# BigBus.net
KiCad netlist of a schematic drawn in EAGLE
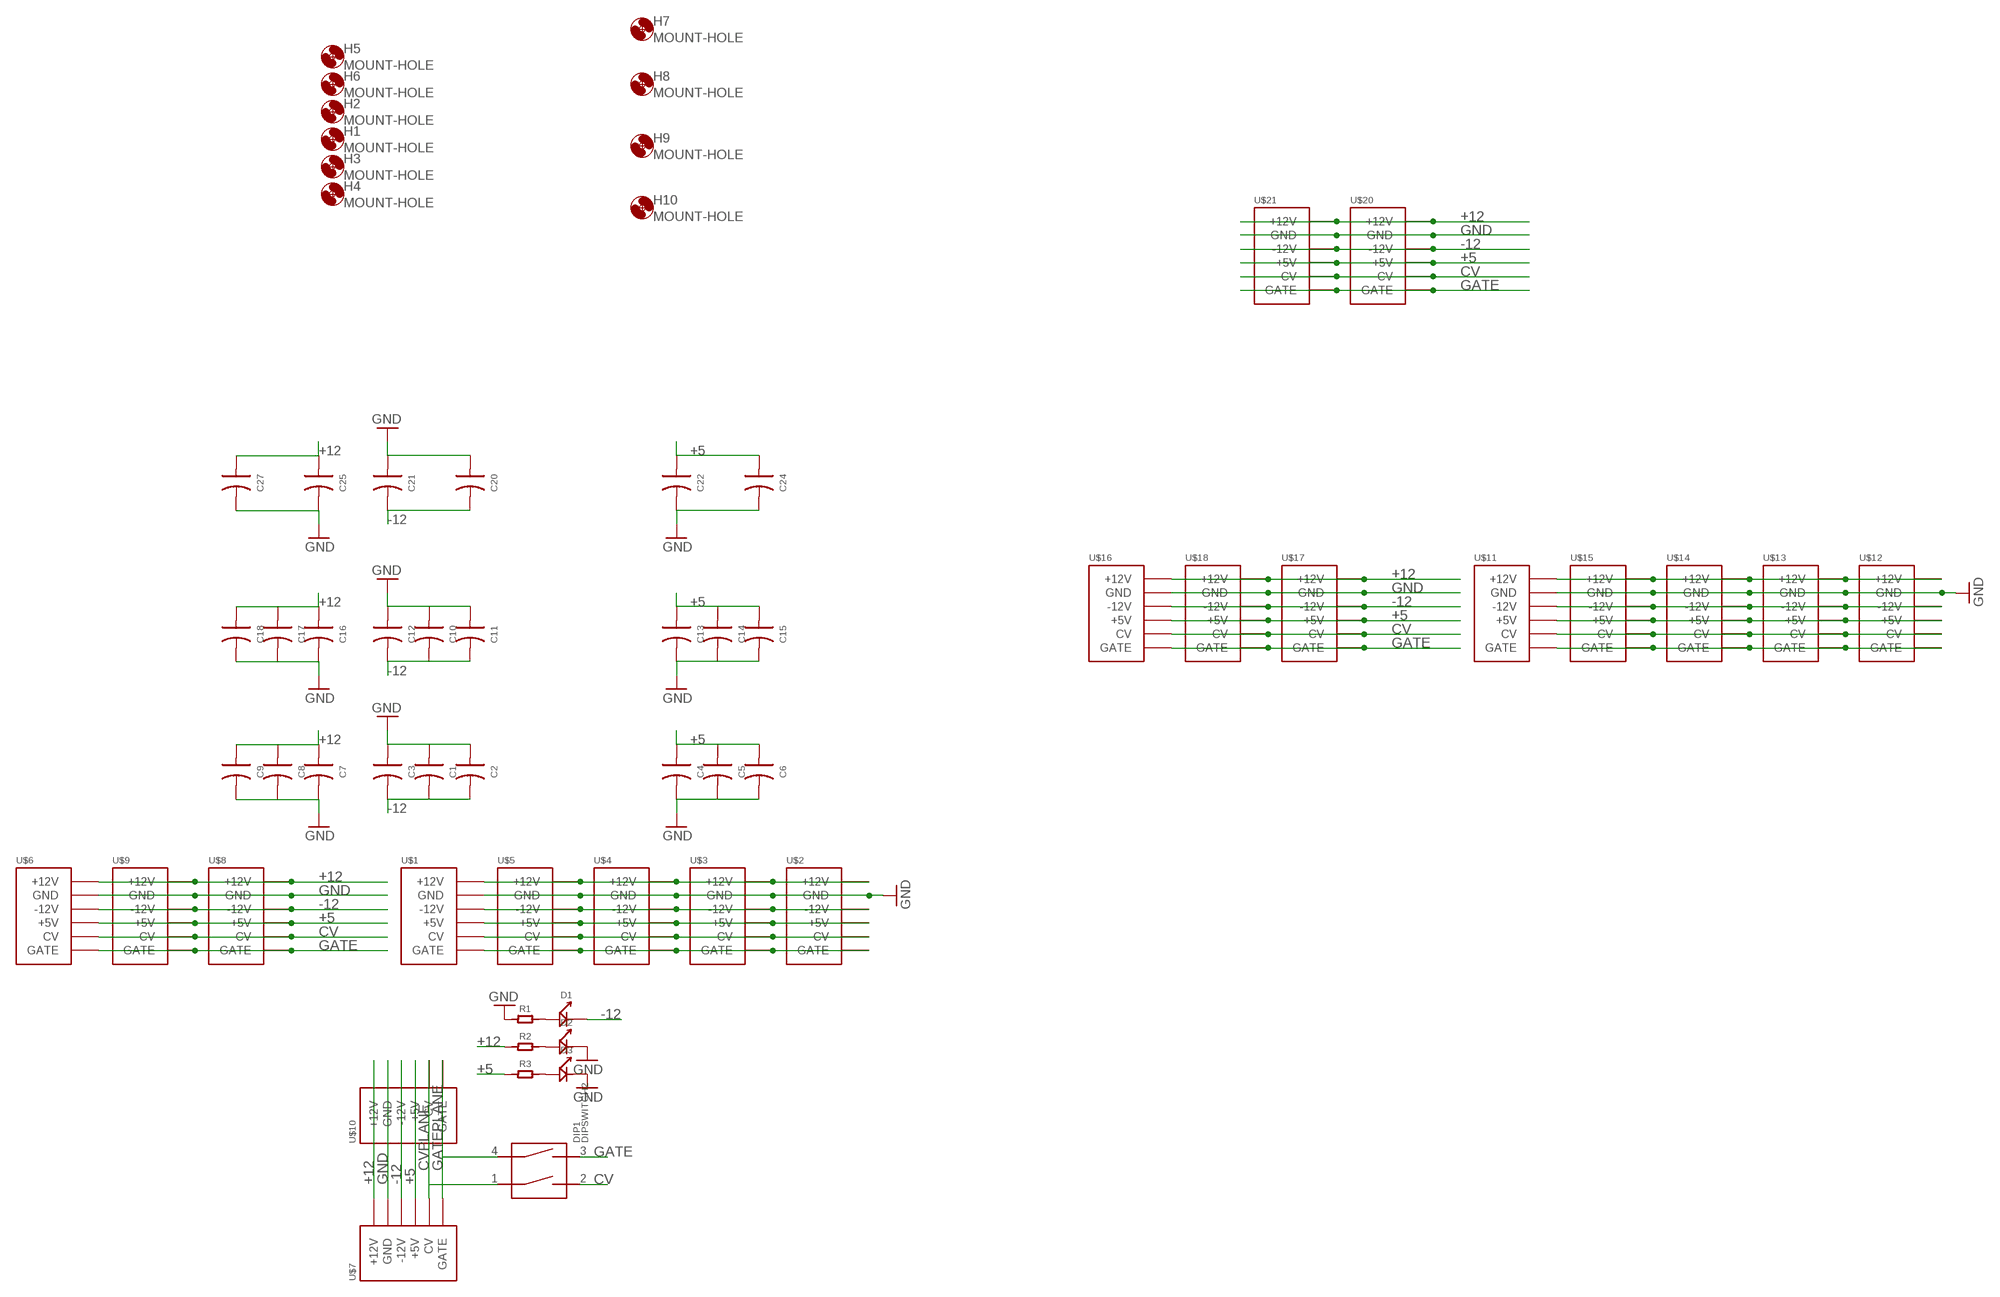
[diagram p0: schematic, sheet 1]

(export (version "E")
  (design (tool "Eeschema 10.0.6"))
  (components
    (comp (ref "C1")
      (value "C-POLAR-A")
      (footprint "eagle-import:AVX-A")
      (libsource (lib "eagle-import") (part "C-POLAR-A"))
    )
    (comp (ref "C2")
      (value "C-POLAR-A")
      (footprint "eagle-import:AVX-A")
      (libsource (lib "eagle-import") (part "C-POLAR-A"))
    )
    (comp (ref "C3")
      (value "C-POLAR-A")
      (footprint "eagle-import:AVX-A")
      (libsource (lib "eagle-import") (part "C-POLAR-A"))
    )
    (comp (ref "C4")
      (value "C-POLAR-A")
      (footprint "eagle-import:AVX-A")
      (libsource (lib "eagle-import") (part "C-POLAR-A"))
    )
    (comp (ref "C5")
      (value "C-POLAR-A")
      (footprint "eagle-import:AVX-A")
      (libsource (lib "eagle-import") (part "C-POLAR-A"))
    )
    (comp (ref "C6")
      (value "C-POLAR-A")
      (footprint "eagle-import:AVX-A")
      (libsource (lib "eagle-import") (part "C-POLAR-A"))
    )
    (comp (ref "C7")
      (value "C-POLAR-A")
      (footprint "eagle-import:AVX-A")
      (libsource (lib "eagle-import") (part "C-POLAR-A"))
    )
    (comp (ref "C8")
      (value "C-POLAR-A")
      (footprint "eagle-import:AVX-A")
      (libsource (lib "eagle-import") (part "C-POLAR-A"))
    )
    (comp (ref "C9")
      (value "C-POLAR-A")
      (footprint "eagle-import:AVX-A")
      (libsource (lib "eagle-import") (part "C-POLAR-A"))
    )
    (comp (ref "C10")
      (value "C-POLAR-A")
      (footprint "eagle-import:AVX-A")
      (libsource (lib "eagle-import") (part "C-POLAR-A"))
    )
    (comp (ref "C11")
      (value "C-POLAR-A")
      (footprint "eagle-import:AVX-A")
      (libsource (lib "eagle-import") (part "C-POLAR-A"))
    )
    (comp (ref "C12")
      (value "C-POLAR-A")
      (footprint "eagle-import:AVX-A")
      (libsource (lib "eagle-import") (part "C-POLAR-A"))
    )
    (comp (ref "C13")
      (value "C-POLAR-A")
      (footprint "eagle-import:AVX-A")
      (libsource (lib "eagle-import") (part "C-POLAR-A"))
    )
    (comp (ref "C14")
      (value "C-POLAR-A")
      (footprint "eagle-import:AVX-A")
      (libsource (lib "eagle-import") (part "C-POLAR-A"))
    )
    (comp (ref "C15")
      (value "C-POLAR-A")
      (footprint "eagle-import:AVX-A")
      (libsource (lib "eagle-import") (part "C-POLAR-A"))
    )
    (comp (ref "C16")
      (value "C-POLAR-A")
      (footprint "eagle-import:AVX-A")
      (libsource (lib "eagle-import") (part "C-POLAR-A"))
    )
    (comp (ref "C17")
      (value "C-POLAR-A")
      (footprint "eagle-import:AVX-A")
      (libsource (lib "eagle-import") (part "C-POLAR-A"))
    )
    (comp (ref "C18")
      (value "C-POLAR-A")
      (footprint "eagle-import:AVX-A")
      (libsource (lib "eagle-import") (part "C-POLAR-A"))
    )
    (comp (ref "C20")
      (value "C-POLAR-A")
      (footprint "eagle-import:AVX-A")
      (libsource (lib "eagle-import") (part "C-POLAR-A"))
    )
    (comp (ref "C21")
      (value "C-POLAR-A")
      (footprint "eagle-import:AVX-A")
      (libsource (lib "eagle-import") (part "C-POLAR-A"))
    )
    (comp (ref "C22")
      (value "C-POLAR-A")
      (footprint "eagle-import:AVX-A")
      (libsource (lib "eagle-import") (part "C-POLAR-A"))
    )
    (comp (ref "C24")
      (value "C-POLAR-A")
      (footprint "eagle-import:AVX-A")
      (libsource (lib "eagle-import") (part "C-POLAR-A"))
    )
    (comp (ref "C25")
      (value "C-POLAR-A")
      (footprint "eagle-import:AVX-A")
      (libsource (lib "eagle-import") (part "C-POLAR-A"))
    )
    (comp (ref "C27")
      (value "C-POLAR-A")
      (footprint "eagle-import:AVX-A")
      (libsource (lib "eagle-import") (part "C-POLAR-A"))
    )
    (comp (ref "D1")
      (value "LED")
      (footprint "eagle-import:LED0603")
      (libsource (lib "eagle-import") (part "LED"))
    )
    (comp (ref "D2")
      (value "LED")
      (footprint "eagle-import:LED0603")
      (libsource (lib "eagle-import") (part "LED"))
    )
    (comp (ref "D3")
      (value "LED")
      (footprint "eagle-import:LED0603")
      (libsource (lib "eagle-import") (part "LED"))
    )
    (comp (ref "DIP1")
      (value "DIPSWITCH2")
      (footprint "eagle-import:DIPSWITCH2")
      (libsource (lib "eagle-import") (part "DIPSWITCH2"))
    )
    (comp (ref "H1")
      (value "MOUNT-HOLE")
      (footprint "eagle-import:3.2-NOMARKINGS-SMALLSAFEZONE")
      (libsource (lib "eagle-import") (part "MOUNT-HOLE"))
    )
    (comp (ref "H2")
      (value "MOUNT-HOLE")
      (footprint "eagle-import:3.2-NOMARKINGS-SMALLSAFEZONE")
      (libsource (lib "eagle-import") (part "MOUNT-HOLE"))
    )
    (comp (ref "H3")
      (value "MOUNT-HOLE")
      (footprint "eagle-import:3.2-NOMARKINGS-SMALLSAFEZONE")
      (libsource (lib "eagle-import") (part "MOUNT-HOLE"))
    )
    (comp (ref "H4")
      (value "MOUNT-HOLE")
      (footprint "eagle-import:3.2-NOMARKINGS-SMALLSAFEZONE")
      (libsource (lib "eagle-import") (part "MOUNT-HOLE"))
    )
    (comp (ref "H5")
      (value "MOUNT-HOLE")
      (footprint "eagle-import:3.2-NOMARKINGS-SMALLSAFEZONE")
      (libsource (lib "eagle-import") (part "MOUNT-HOLE"))
    )
    (comp (ref "H6")
      (value "MOUNT-HOLE")
      (footprint "eagle-import:3.2-NOMARKINGS-SMALLSAFEZONE")
      (libsource (lib "eagle-import") (part "MOUNT-HOLE"))
    )
    (comp (ref "H7")
      (value "MOUNT-HOLE")
      (footprint "eagle-import:3.2-NOMARKINGS-SMALLSAFEZONE")
      (libsource (lib "eagle-import") (part "MOUNT-HOLE"))
    )
    (comp (ref "H8")
      (value "MOUNT-HOLE")
      (footprint "eagle-import:3.2-NOMARKINGS-SMALLSAFEZONE")
      (libsource (lib "eagle-import") (part "MOUNT-HOLE"))
    )
    (comp (ref "H9")
      (value "MOUNT-HOLE")
      (footprint "eagle-import:3.2-NOMARKINGS-SMALLSAFEZONE")
      (libsource (lib "eagle-import") (part "MOUNT-HOLE"))
    )
    (comp (ref "H10")
      (value "MOUNT-HOLE")
      (footprint "eagle-import:3.2-NOMARKINGS-SMALLSAFEZONE")
      (libsource (lib "eagle-import") (part "MOUNT-HOLE"))
    )
    (comp (ref "R1")
      (value "R-0603")
      (footprint "eagle-import:R0603")
      (libsource (lib "eagle-import") (part "R-0603"))
    )
    (comp (ref "R2")
      (value "R-0603")
      (footprint "eagle-import:R0603")
      (libsource (lib "eagle-import") (part "R-0603"))
    )
    (comp (ref "R3")
      (value "R-0603")
      (footprint "eagle-import:R0603")
      (libsource (lib "eagle-import") (part "R-0603"))
    )
    (comp (ref "U$1")
      (value "POWER")
      (footprint "eagle-import:POWER_16")
      (libsource (lib "eagle-import") (part "POWER"))
    )
    (comp (ref "U$2")
      (value "POWER")
      (footprint "eagle-import:POWER_16")
      (libsource (lib "eagle-import") (part "POWER"))
    )
    (comp (ref "U$3")
      (value "POWER")
      (footprint "eagle-import:POWER_16")
      (libsource (lib "eagle-import") (part "POWER"))
    )
    (comp (ref "U$4")
      (value "POWER")
      (footprint "eagle-import:POWER_16")
      (libsource (lib "eagle-import") (part "POWER"))
    )
    (comp (ref "U$5")
      (value "POWER")
      (footprint "eagle-import:POWER_16")
      (libsource (lib "eagle-import") (part "POWER"))
    )
    (comp (ref "U$6")
      (value "POWER")
      (footprint "eagle-import:POWER_16")
      (libsource (lib "eagle-import") (part "POWER"))
    )
    (comp (ref "U$7")
      (value "POWER")
      (footprint "eagle-import:POWER_16")
      (libsource (lib "eagle-import") (part "POWER"))
    )
    (comp (ref "U$8")
      (value "POWER")
      (footprint "eagle-import:POWER_16")
      (libsource (lib "eagle-import") (part "POWER"))
    )
    (comp (ref "U$9")
      (value "POWER")
      (footprint "eagle-import:POWER_16")
      (libsource (lib "eagle-import") (part "POWER"))
    )
    (comp (ref "U$10")
      (value "POWER")
      (footprint "eagle-import:POWER_16")
      (libsource (lib "eagle-import") (part "POWER"))
    )
    (comp (ref "U$11")
      (value "POWER")
      (footprint "eagle-import:POWER_16")
      (libsource (lib "eagle-import") (part "POWER"))
    )
    (comp (ref "U$12")
      (value "POWER")
      (footprint "eagle-import:POWER_16")
      (libsource (lib "eagle-import") (part "POWER"))
    )
    (comp (ref "U$13")
      (value "POWER")
      (footprint "eagle-import:POWER_16")
      (libsource (lib "eagle-import") (part "POWER"))
    )
    (comp (ref "U$14")
      (value "POWER")
      (footprint "eagle-import:POWER_16")
      (libsource (lib "eagle-import") (part "POWER"))
    )
    (comp (ref "U$15")
      (value "POWER")
      (footprint "eagle-import:POWER_16")
      (libsource (lib "eagle-import") (part "POWER"))
    )
    (comp (ref "U$16")
      (value "POWER")
      (footprint "eagle-import:POWER_16")
      (libsource (lib "eagle-import") (part "POWER"))
    )
    (comp (ref "U$17")
      (value "POWER")
      (footprint "eagle-import:POWER_16")
      (libsource (lib "eagle-import") (part "POWER"))
    )
    (comp (ref "U$18")
      (value "POWER")
      (footprint "eagle-import:POWER_16")
      (libsource (lib "eagle-import") (part "POWER"))
    )
    (comp (ref "U$20")
      (value "POWER")
      (footprint "eagle-import:POWER_16")
      (libsource (lib "eagle-import") (part "POWER"))
    )
    (comp (ref "U$21")
      (value "POWER")
      (footprint "eagle-import:POWER_16")
      (libsource (lib "eagle-import") (part "POWER"))
    )
  )
  (nets
    (net (code "1") (name "/+5") (class "Default")
      (node (ref "C13") (pin "+") (pinfunction "1_+") (pintype "bidirectional"))
      (node (ref "C14") (pin "+") (pinfunction "1_+") (pintype "bidirectional"))
      (node (ref "C15") (pin "+") (pinfunction "1_+") (pintype "bidirectional"))
      (node (ref "C22") (pin "+") (pinfunction "1_+") (pintype "bidirectional"))
      (node (ref "C24") (pin "+") (pinfunction "1_+") (pintype "bidirectional"))
      (node (ref "C4") (pin "+") (pinfunction "1_+") (pintype "bidirectional"))
      (node (ref "C5") (pin "+") (pinfunction "1_+") (pintype "bidirectional"))
      (node (ref "C6") (pin "+") (pinfunction "1_+") (pintype "bidirectional"))
      (node (ref "R3") (pin "1") (pinfunction "1_1") (pintype "bidirectional"))
      (node (ref "U$1") (pin "11") (pinfunction "+5V_11") (pintype "bidirectional"))
      (node (ref "U$1") (pin "12") (pinfunction "+5V_12") (pintype "bidirectional"))
      (node (ref "U$10") (pin "11") (pinfunction "+5V_11") (pintype "bidirectional"))
      (node (ref "U$10") (pin "12") (pinfunction "+5V_12") (pintype "bidirectional"))
      (node (ref "U$11") (pin "11") (pinfunction "+5V_11") (pintype "bidirectional"))
      (node (ref "U$11") (pin "12") (pinfunction "+5V_12") (pintype "bidirectional"))
      (node (ref "U$12") (pin "11") (pinfunction "+5V_11") (pintype "bidirectional"))
      (node (ref "U$12") (pin "12") (pinfunction "+5V_12") (pintype "bidirectional"))
      (node (ref "U$13") (pin "11") (pinfunction "+5V_11") (pintype "bidirectional"))
      (node (ref "U$13") (pin "12") (pinfunction "+5V_12") (pintype "bidirectional"))
      (node (ref "U$14") (pin "11") (pinfunction "+5V_11") (pintype "bidirectional"))
      (node (ref "U$14") (pin "12") (pinfunction "+5V_12") (pintype "bidirectional"))
      (node (ref "U$15") (pin "11") (pinfunction "+5V_11") (pintype "bidirectional"))
      (node (ref "U$15") (pin "12") (pinfunction "+5V_12") (pintype "bidirectional"))
      (node (ref "U$16") (pin "11") (pinfunction "+5V_11") (pintype "bidirectional"))
      (node (ref "U$16") (pin "12") (pinfunction "+5V_12") (pintype "bidirectional"))
      (node (ref "U$17") (pin "11") (pinfunction "+5V_11") (pintype "bidirectional"))
      (node (ref "U$17") (pin "12") (pinfunction "+5V_12") (pintype "bidirectional"))
      (node (ref "U$18") (pin "11") (pinfunction "+5V_11") (pintype "bidirectional"))
      (node (ref "U$18") (pin "12") (pinfunction "+5V_12") (pintype "bidirectional"))
      (node (ref "U$2") (pin "11") (pinfunction "+5V_11") (pintype "bidirectional"))
      (node (ref "U$2") (pin "12") (pinfunction "+5V_12") (pintype "bidirectional"))
      (node (ref "U$20") (pin "11") (pinfunction "+5V_11") (pintype "bidirectional"))
      (node (ref "U$20") (pin "12") (pinfunction "+5V_12") (pintype "bidirectional"))
      (node (ref "U$21") (pin "11") (pinfunction "+5V_11") (pintype "bidirectional"))
      (node (ref "U$21") (pin "12") (pinfunction "+5V_12") (pintype "bidirectional"))
      (node (ref "U$3") (pin "11") (pinfunction "+5V_11") (pintype "bidirectional"))
      (node (ref "U$3") (pin "12") (pinfunction "+5V_12") (pintype "bidirectional"))
      (node (ref "U$4") (pin "11") (pinfunction "+5V_11") (pintype "bidirectional"))
      (node (ref "U$4") (pin "12") (pinfunction "+5V_12") (pintype "bidirectional"))
      (node (ref "U$5") (pin "11") (pinfunction "+5V_11") (pintype "bidirectional"))
      (node (ref "U$5") (pin "12") (pinfunction "+5V_12") (pintype "bidirectional"))
      (node (ref "U$6") (pin "11") (pinfunction "+5V_11") (pintype "bidirectional"))
      (node (ref "U$6") (pin "12") (pinfunction "+5V_12") (pintype "bidirectional"))
      (node (ref "U$7") (pin "11") (pinfunction "+5V_11") (pintype "bidirectional"))
      (node (ref "U$7") (pin "12") (pinfunction "+5V_12") (pintype "bidirectional"))
      (node (ref "U$8") (pin "11") (pinfunction "+5V_11") (pintype "bidirectional"))
      (node (ref "U$8") (pin "12") (pinfunction "+5V_12") (pintype "bidirectional"))
      (node (ref "U$9") (pin "11") (pinfunction "+5V_11") (pintype "bidirectional"))
      (node (ref "U$9") (pin "12") (pinfunction "+5V_12") (pintype "bidirectional"))
    )
    (net (code "2") (name "/+12") (class "Default")
      (node (ref "C16") (pin "+") (pinfunction "1_+") (pintype "bidirectional"))
      (node (ref "C17") (pin "+") (pinfunction "1_+") (pintype "bidirectional"))
      (node (ref "C18") (pin "+") (pinfunction "1_+") (pintype "bidirectional"))
      (node (ref "C25") (pin "+") (pinfunction "1_+") (pintype "bidirectional"))
      (node (ref "C27") (pin "+") (pinfunction "1_+") (pintype "bidirectional"))
      (node (ref "C7") (pin "+") (pinfunction "1_+") (pintype "bidirectional"))
      (node (ref "C8") (pin "+") (pinfunction "1_+") (pintype "bidirectional"))
      (node (ref "C9") (pin "+") (pinfunction "1_+") (pintype "bidirectional"))
      (node (ref "R2") (pin "1") (pinfunction "1_1") (pintype "bidirectional"))
      (node (ref "U$1") (pin "10") (pinfunction "+12V_10") (pintype "bidirectional"))
      (node (ref "U$1") (pin "9") (pinfunction "+12V_9") (pintype "bidirectional"))
      (node (ref "U$10") (pin "10") (pinfunction "+12V_10") (pintype "bidirectional"))
      (node (ref "U$10") (pin "9") (pinfunction "+12V_9") (pintype "bidirectional"))
      (node (ref "U$11") (pin "10") (pinfunction "+12V_10") (pintype "bidirectional"))
      (node (ref "U$11") (pin "9") (pinfunction "+12V_9") (pintype "bidirectional"))
      (node (ref "U$12") (pin "10") (pinfunction "+12V_10") (pintype "bidirectional"))
      (node (ref "U$12") (pin "9") (pinfunction "+12V_9") (pintype "bidirectional"))
      (node (ref "U$13") (pin "10") (pinfunction "+12V_10") (pintype "bidirectional"))
      (node (ref "U$13") (pin "9") (pinfunction "+12V_9") (pintype "bidirectional"))
      (node (ref "U$14") (pin "10") (pinfunction "+12V_10") (pintype "bidirectional"))
      (node (ref "U$14") (pin "9") (pinfunction "+12V_9") (pintype "bidirectional"))
      (node (ref "U$15") (pin "10") (pinfunction "+12V_10") (pintype "bidirectional"))
      (node (ref "U$15") (pin "9") (pinfunction "+12V_9") (pintype "bidirectional"))
      (node (ref "U$16") (pin "10") (pinfunction "+12V_10") (pintype "bidirectional"))
      (node (ref "U$16") (pin "9") (pinfunction "+12V_9") (pintype "bidirectional"))
      (node (ref "U$17") (pin "10") (pinfunction "+12V_10") (pintype "bidirectional"))
      (node (ref "U$17") (pin "9") (pinfunction "+12V_9") (pintype "bidirectional"))
      (node (ref "U$18") (pin "10") (pinfunction "+12V_10") (pintype "bidirectional"))
      (node (ref "U$18") (pin "9") (pinfunction "+12V_9") (pintype "bidirectional"))
      (node (ref "U$2") (pin "10") (pinfunction "+12V_10") (pintype "bidirectional"))
      (node (ref "U$2") (pin "9") (pinfunction "+12V_9") (pintype "bidirectional"))
      (node (ref "U$20") (pin "10") (pinfunction "+12V_10") (pintype "bidirectional"))
      (node (ref "U$20") (pin "9") (pinfunction "+12V_9") (pintype "bidirectional"))
      (node (ref "U$21") (pin "10") (pinfunction "+12V_10") (pintype "bidirectional"))
      (node (ref "U$21") (pin "9") (pinfunction "+12V_9") (pintype "bidirectional"))
      (node (ref "U$3") (pin "10") (pinfunction "+12V_10") (pintype "bidirectional"))
      (node (ref "U$3") (pin "9") (pinfunction "+12V_9") (pintype "bidirectional"))
      (node (ref "U$4") (pin "10") (pinfunction "+12V_10") (pintype "bidirectional"))
      (node (ref "U$4") (pin "9") (pinfunction "+12V_9") (pintype "bidirectional"))
      (node (ref "U$5") (pin "10") (pinfunction "+12V_10") (pintype "bidirectional"))
      (node (ref "U$5") (pin "9") (pinfunction "+12V_9") (pintype "bidirectional"))
      (node (ref "U$6") (pin "10") (pinfunction "+12V_10") (pintype "bidirectional"))
      (node (ref "U$6") (pin "9") (pinfunction "+12V_9") (pintype "bidirectional"))
      (node (ref "U$7") (pin "10") (pinfunction "+12V_10") (pintype "bidirectional"))
      (node (ref "U$7") (pin "9") (pinfunction "+12V_9") (pintype "bidirectional"))
      (node (ref "U$8") (pin "10") (pinfunction "+12V_10") (pintype "bidirectional"))
      (node (ref "U$8") (pin "9") (pinfunction "+12V_9") (pintype "bidirectional"))
      (node (ref "U$9") (pin "10") (pinfunction "+12V_10") (pintype "bidirectional"))
      (node (ref "U$9") (pin "9") (pinfunction "+12V_9") (pintype "bidirectional"))
    )
    (net (code "3") (name "/-12") (class "Default")
      (node (ref "C1") (pin "-") (pinfunction "2_-") (pintype "bidirectional"))
      (node (ref "C10") (pin "-") (pinfunction "2_-") (pintype "bidirectional"))
      (node (ref "C11") (pin "-") (pinfunction "2_-") (pintype "bidirectional"))
      (node (ref "C12") (pin "-") (pinfunction "2_-") (pintype "bidirectional"))
      (node (ref "C2") (pin "-") (pinfunction "2_-") (pintype "bidirectional"))
      (node (ref "C20") (pin "-") (pinfunction "2_-") (pintype "bidirectional"))
      (node (ref "C21") (pin "-") (pinfunction "2_-") (pintype "bidirectional"))
      (node (ref "C3") (pin "-") (pinfunction "2_-") (pintype "bidirectional"))
      (node (ref "D1") (pin "-") (pinfunction "-_-") (pintype "passive"))
      (node (ref "U$1") (pin "1") (pinfunction "-12V_1") (pintype "bidirectional"))
      (node (ref "U$1") (pin "2") (pinfunction "-12V_2") (pintype "bidirectional"))
      (node (ref "U$10") (pin "1") (pinfunction "-12V_1") (pintype "bidirectional"))
      (node (ref "U$10") (pin "2") (pinfunction "-12V_2") (pintype "bidirectional"))
      (node (ref "U$11") (pin "1") (pinfunction "-12V_1") (pintype "bidirectional"))
      (node (ref "U$11") (pin "2") (pinfunction "-12V_2") (pintype "bidirectional"))
      (node (ref "U$12") (pin "1") (pinfunction "-12V_1") (pintype "bidirectional"))
      (node (ref "U$12") (pin "2") (pinfunction "-12V_2") (pintype "bidirectional"))
      (node (ref "U$13") (pin "1") (pinfunction "-12V_1") (pintype "bidirectional"))
      (node (ref "U$13") (pin "2") (pinfunction "-12V_2") (pintype "bidirectional"))
      (node (ref "U$14") (pin "1") (pinfunction "-12V_1") (pintype "bidirectional"))
      (node (ref "U$14") (pin "2") (pinfunction "-12V_2") (pintype "bidirectional"))
      (node (ref "U$15") (pin "1") (pinfunction "-12V_1") (pintype "bidirectional"))
      (node (ref "U$15") (pin "2") (pinfunction "-12V_2") (pintype "bidirectional"))
      (node (ref "U$16") (pin "1") (pinfunction "-12V_1") (pintype "bidirectional"))
      (node (ref "U$16") (pin "2") (pinfunction "-12V_2") (pintype "bidirectional"))
      (node (ref "U$17") (pin "1") (pinfunction "-12V_1") (pintype "bidirectional"))
      (node (ref "U$17") (pin "2") (pinfunction "-12V_2") (pintype "bidirectional"))
      (node (ref "U$18") (pin "1") (pinfunction "-12V_1") (pintype "bidirectional"))
      (node (ref "U$18") (pin "2") (pinfunction "-12V_2") (pintype "bidirectional"))
      (node (ref "U$2") (pin "1") (pinfunction "-12V_1") (pintype "bidirectional"))
      (node (ref "U$2") (pin "2") (pinfunction "-12V_2") (pintype "bidirectional"))
      (node (ref "U$20") (pin "1") (pinfunction "-12V_1") (pintype "bidirectional"))
      (node (ref "U$20") (pin "2") (pinfunction "-12V_2") (pintype "bidirectional"))
      (node (ref "U$21") (pin "1") (pinfunction "-12V_1") (pintype "bidirectional"))
      (node (ref "U$21") (pin "2") (pinfunction "-12V_2") (pintype "bidirectional"))
      (node (ref "U$3") (pin "1") (pinfunction "-12V_1") (pintype "bidirectional"))
      (node (ref "U$3") (pin "2") (pinfunction "-12V_2") (pintype "bidirectional"))
      (node (ref "U$4") (pin "1") (pinfunction "-12V_1") (pintype "bidirectional"))
      (node (ref "U$4") (pin "2") (pinfunction "-12V_2") (pintype "bidirectional"))
      (node (ref "U$5") (pin "1") (pinfunction "-12V_1") (pintype "bidirectional"))
      (node (ref "U$5") (pin "2") (pinfunction "-12V_2") (pintype "bidirectional"))
      (node (ref "U$6") (pin "1") (pinfunction "-12V_1") (pintype "bidirectional"))
      (node (ref "U$6") (pin "2") (pinfunction "-12V_2") (pintype "bidirectional"))
      (node (ref "U$7") (pin "1") (pinfunction "-12V_1") (pintype "bidirectional"))
      (node (ref "U$7") (pin "2") (pinfunction "-12V_2") (pintype "bidirectional"))
      (node (ref "U$8") (pin "1") (pinfunction "-12V_1") (pintype "bidirectional"))
      (node (ref "U$8") (pin "2") (pinfunction "-12V_2") (pintype "bidirectional"))
      (node (ref "U$9") (pin "1") (pinfunction "-12V_1") (pintype "bidirectional"))
      (node (ref "U$9") (pin "2") (pinfunction "-12V_2") (pintype "bidirectional"))
    )
    (net (code "4") (name "/CV") (class "Default")
      (node (ref "DIP1") (pin "2") (pinfunction "P$2_2") (pintype "bidirectional"))
      (node (ref "U$1") (pin "13") (pinfunction "CV_13") (pintype "bidirectional"))
      (node (ref "U$1") (pin "14") (pinfunction "CV_14") (pintype "bidirectional"))
      (node (ref "U$11") (pin "13") (pinfunction "CV_13") (pintype "bidirectional"))
      (node (ref "U$11") (pin "14") (pinfunction "CV_14") (pintype "bidirectional"))
      (node (ref "U$12") (pin "13") (pinfunction "CV_13") (pintype "bidirectional"))
      (node (ref "U$12") (pin "14") (pinfunction "CV_14") (pintype "bidirectional"))
      (node (ref "U$13") (pin "13") (pinfunction "CV_13") (pintype "bidirectional"))
      (node (ref "U$13") (pin "14") (pinfunction "CV_14") (pintype "bidirectional"))
      (node (ref "U$14") (pin "13") (pinfunction "CV_13") (pintype "bidirectional"))
      (node (ref "U$14") (pin "14") (pinfunction "CV_14") (pintype "bidirectional"))
      (node (ref "U$15") (pin "13") (pinfunction "CV_13") (pintype "bidirectional"))
      (node (ref "U$15") (pin "14") (pinfunction "CV_14") (pintype "bidirectional"))
      (node (ref "U$16") (pin "13") (pinfunction "CV_13") (pintype "bidirectional"))
      (node (ref "U$16") (pin "14") (pinfunction "CV_14") (pintype "bidirectional"))
      (node (ref "U$17") (pin "13") (pinfunction "CV_13") (pintype "bidirectional"))
      (node (ref "U$17") (pin "14") (pinfunction "CV_14") (pintype "bidirectional"))
      (node (ref "U$18") (pin "13") (pinfunction "CV_13") (pintype "bidirectional"))
      (node (ref "U$18") (pin "14") (pinfunction "CV_14") (pintype "bidirectional"))
      (node (ref "U$2") (pin "13") (pinfunction "CV_13") (pintype "bidirectional"))
      (node (ref "U$2") (pin "14") (pinfunction "CV_14") (pintype "bidirectional"))
      (node (ref "U$20") (pin "13") (pinfunction "CV_13") (pintype "bidirectional"))
      (node (ref "U$20") (pin "14") (pinfunction "CV_14") (pintype "bidirectional"))
      (node (ref "U$21") (pin "13") (pinfunction "CV_13") (pintype "bidirectional"))
      (node (ref "U$21") (pin "14") (pinfunction "CV_14") (pintype "bidirectional"))
      (node (ref "U$3") (pin "13") (pinfunction "CV_13") (pintype "bidirectional"))
      (node (ref "U$3") (pin "14") (pinfunction "CV_14") (pintype "bidirectional"))
      (node (ref "U$4") (pin "13") (pinfunction "CV_13") (pintype "bidirectional"))
      (node (ref "U$4") (pin "14") (pinfunction "CV_14") (pintype "bidirectional"))
      (node (ref "U$5") (pin "13") (pinfunction "CV_13") (pintype "bidirectional"))
      (node (ref "U$5") (pin "14") (pinfunction "CV_14") (pintype "bidirectional"))
      (node (ref "U$6") (pin "13") (pinfunction "CV_13") (pintype "bidirectional"))
      (node (ref "U$6") (pin "14") (pinfunction "CV_14") (pintype "bidirectional"))
      (node (ref "U$8") (pin "13") (pinfunction "CV_13") (pintype "bidirectional"))
      (node (ref "U$8") (pin "14") (pinfunction "CV_14") (pintype "bidirectional"))
      (node (ref "U$9") (pin "13") (pinfunction "CV_13") (pintype "bidirectional"))
      (node (ref "U$9") (pin "14") (pinfunction "CV_14") (pintype "bidirectional"))
    )
    (net (code "5") (name "/CVPLANE") (class "Default")
      (node (ref "DIP1") (pin "1") (pinfunction "P$1_1") (pintype "bidirectional"))
      (node (ref "U$10") (pin "13") (pinfunction "CV_13") (pintype "bidirectional"))
      (node (ref "U$10") (pin "14") (pinfunction "CV_14") (pintype "bidirectional"))
      (node (ref "U$7") (pin "13") (pinfunction "CV_13") (pintype "bidirectional"))
      (node (ref "U$7") (pin "14") (pinfunction "CV_14") (pintype "bidirectional"))
    )
    (net (code "6") (name "/GATE") (class "Default")
      (node (ref "DIP1") (pin "3") (pinfunction "P$3_3") (pintype "bidirectional"))
      (node (ref "U$1") (pin "15") (pinfunction "GATE_15") (pintype "bidirectional"))
      (node (ref "U$1") (pin "16") (pinfunction "GATE_16") (pintype "bidirectional"))
      (node (ref "U$11") (pin "15") (pinfunction "GATE_15") (pintype "bidirectional"))
      (node (ref "U$11") (pin "16") (pinfunction "GATE_16") (pintype "bidirectional"))
      (node (ref "U$12") (pin "15") (pinfunction "GATE_15") (pintype "bidirectional"))
      (node (ref "U$12") (pin "16") (pinfunction "GATE_16") (pintype "bidirectional"))
      (node (ref "U$13") (pin "15") (pinfunction "GATE_15") (pintype "bidirectional"))
      (node (ref "U$13") (pin "16") (pinfunction "GATE_16") (pintype "bidirectional"))
      (node (ref "U$14") (pin "15") (pinfunction "GATE_15") (pintype "bidirectional"))
      (node (ref "U$14") (pin "16") (pinfunction "GATE_16") (pintype "bidirectional"))
      (node (ref "U$15") (pin "15") (pinfunction "GATE_15") (pintype "bidirectional"))
      (node (ref "U$15") (pin "16") (pinfunction "GATE_16") (pintype "bidirectional"))
      (node (ref "U$16") (pin "15") (pinfunction "GATE_15") (pintype "bidirectional"))
      (node (ref "U$16") (pin "16") (pinfunction "GATE_16") (pintype "bidirectional"))
      (node (ref "U$17") (pin "15") (pinfunction "GATE_15") (pintype "bidirectional"))
      (node (ref "U$17") (pin "16") (pinfunction "GATE_16") (pintype "bidirectional"))
      (node (ref "U$18") (pin "15") (pinfunction "GATE_15") (pintype "bidirectional"))
      (node (ref "U$18") (pin "16") (pinfunction "GATE_16") (pintype "bidirectional"))
      (node (ref "U$2") (pin "15") (pinfunction "GATE_15") (pintype "bidirectional"))
      (node (ref "U$2") (pin "16") (pinfunction "GATE_16") (pintype "bidirectional"))
      (node (ref "U$20") (pin "15") (pinfunction "GATE_15") (pintype "bidirectional"))
      (node (ref "U$20") (pin "16") (pinfunction "GATE_16") (pintype "bidirectional"))
      (node (ref "U$21") (pin "15") (pinfunction "GATE_15") (pintype "bidirectional"))
      (node (ref "U$21") (pin "16") (pinfunction "GATE_16") (pintype "bidirectional"))
      (node (ref "U$3") (pin "15") (pinfunction "GATE_15") (pintype "bidirectional"))
      (node (ref "U$3") (pin "16") (pinfunction "GATE_16") (pintype "bidirectional"))
      (node (ref "U$4") (pin "15") (pinfunction "GATE_15") (pintype "bidirectional"))
      (node (ref "U$4") (pin "16") (pinfunction "GATE_16") (pintype "bidirectional"))
      (node (ref "U$5") (pin "15") (pinfunction "GATE_15") (pintype "bidirectional"))
      (node (ref "U$5") (pin "16") (pinfunction "GATE_16") (pintype "bidirectional"))
      (node (ref "U$6") (pin "15") (pinfunction "GATE_15") (pintype "bidirectional"))
      (node (ref "U$6") (pin "16") (pinfunction "GATE_16") (pintype "bidirectional"))
      (node (ref "U$8") (pin "15") (pinfunction "GATE_15") (pintype "bidirectional"))
      (node (ref "U$8") (pin "16") (pinfunction "GATE_16") (pintype "bidirectional"))
      (node (ref "U$9") (pin "15") (pinfunction "GATE_15") (pintype "bidirectional"))
      (node (ref "U$9") (pin "16") (pinfunction "GATE_16") (pintype "bidirectional"))
    )
    (net (code "7") (name "/GATEPLANE") (class "Default")
      (node (ref "DIP1") (pin "4") (pinfunction "P$4_4") (pintype "bidirectional"))
      (node (ref "U$10") (pin "15") (pinfunction "GATE_15") (pintype "bidirectional"))
      (node (ref "U$10") (pin "16") (pinfunction "GATE_16") (pintype "bidirectional"))
      (node (ref "U$7") (pin "15") (pinfunction "GATE_15") (pintype "bidirectional"))
      (node (ref "U$7") (pin "16") (pinfunction "GATE_16") (pintype "bidirectional"))
    )
    (net (code "8") (name "GND") (class "Default")
      (node (ref "C1") (pin "+") (pinfunction "1_+") (pintype "bidirectional"))
      (node (ref "C10") (pin "+") (pinfunction "1_+") (pintype "bidirectional"))
      (node (ref "C11") (pin "+") (pinfunction "1_+") (pintype "bidirectional"))
      (node (ref "C12") (pin "+") (pinfunction "1_+") (pintype "bidirectional"))
      (node (ref "C13") (pin "-") (pinfunction "2_-") (pintype "bidirectional"))
      (node (ref "C14") (pin "-") (pinfunction "2_-") (pintype "bidirectional"))
      (node (ref "C15") (pin "-") (pinfunction "2_-") (pintype "bidirectional"))
      (node (ref "C16") (pin "-") (pinfunction "2_-") (pintype "bidirectional"))
      (node (ref "C17") (pin "-") (pinfunction "2_-") (pintype "bidirectional"))
      (node (ref "C18") (pin "-") (pinfunction "2_-") (pintype "bidirectional"))
      (node (ref "C2") (pin "+") (pinfunction "1_+") (pintype "bidirectional"))
      (node (ref "C20") (pin "+") (pinfunction "1_+") (pintype "bidirectional"))
      (node (ref "C21") (pin "+") (pinfunction "1_+") (pintype "bidirectional"))
      (node (ref "C22") (pin "-") (pinfunction "2_-") (pintype "bidirectional"))
      (node (ref "C24") (pin "-") (pinfunction "2_-") (pintype "bidirectional"))
      (node (ref "C25") (pin "-") (pinfunction "2_-") (pintype "bidirectional"))
      (node (ref "C27") (pin "-") (pinfunction "2_-") (pintype "bidirectional"))
      (node (ref "C3") (pin "+") (pinfunction "1_+") (pintype "bidirectional"))
      (node (ref "C4") (pin "-") (pinfunction "2_-") (pintype "bidirectional"))
      (node (ref "C5") (pin "-") (pinfunction "2_-") (pintype "bidirectional"))
      (node (ref "C6") (pin "-") (pinfunction "2_-") (pintype "bidirectional"))
      (node (ref "C7") (pin "-") (pinfunction "2_-") (pintype "bidirectional"))
      (node (ref "C8") (pin "-") (pinfunction "2_-") (pintype "bidirectional"))
      (node (ref "C9") (pin "-") (pinfunction "2_-") (pintype "bidirectional"))
      (node (ref "D2") (pin "-") (pinfunction "-_-") (pintype "passive"))
      (node (ref "D3") (pin "-") (pinfunction "-_-") (pintype "passive"))
      (node (ref "R1") (pin "1") (pinfunction "1_1") (pintype "bidirectional"))
      (node (ref "U$1") (pin "3") (pinfunction "GND_3") (pintype "bidirectional"))
      (node (ref "U$1") (pin "4") (pinfunction "GND_4") (pintype "bidirectional"))
      (node (ref "U$1") (pin "5") (pinfunction "GND_5") (pintype "bidirectional"))
      (node (ref "U$1") (pin "6") (pinfunction "GND_6") (pintype "bidirectional"))
      (node (ref "U$1") (pin "7") (pinfunction "GND_7") (pintype "bidirectional"))
      (node (ref "U$1") (pin "8") (pinfunction "GND_8") (pintype "bidirectional"))
      (node (ref "U$10") (pin "3") (pinfunction "GND_3") (pintype "bidirectional"))
      (node (ref "U$10") (pin "4") (pinfunction "GND_4") (pintype "bidirectional"))
      (node (ref "U$10") (pin "5") (pinfunction "GND_5") (pintype "bidirectional"))
      (node (ref "U$10") (pin "6") (pinfunction "GND_6") (pintype "bidirectional"))
      (node (ref "U$10") (pin "7") (pinfunction "GND_7") (pintype "bidirectional"))
      (node (ref "U$10") (pin "8") (pinfunction "GND_8") (pintype "bidirectional"))
      (node (ref "U$11") (pin "3") (pinfunction "GND_3") (pintype "bidirectional"))
      (node (ref "U$11") (pin "4") (pinfunction "GND_4") (pintype "bidirectional"))
      (node (ref "U$11") (pin "5") (pinfunction "GND_5") (pintype "bidirectional"))
      (node (ref "U$11") (pin "6") (pinfunction "GND_6") (pintype "bidirectional"))
      (node (ref "U$11") (pin "7") (pinfunction "GND_7") (pintype "bidirectional"))
      (node (ref "U$11") (pin "8") (pinfunction "GND_8") (pintype "bidirectional"))
      (node (ref "U$12") (pin "3") (pinfunction "GND_3") (pintype "bidirectional"))
      (node (ref "U$12") (pin "4") (pinfunction "GND_4") (pintype "bidirectional"))
      (node (ref "U$12") (pin "5") (pinfunction "GND_5") (pintype "bidirectional"))
      (node (ref "U$12") (pin "6") (pinfunction "GND_6") (pintype "bidirectional"))
      (node (ref "U$12") (pin "7") (pinfunction "GND_7") (pintype "bidirectional"))
      (node (ref "U$12") (pin "8") (pinfunction "GND_8") (pintype "bidirectional"))
      (node (ref "U$13") (pin "3") (pinfunction "GND_3") (pintype "bidirectional"))
      (node (ref "U$13") (pin "4") (pinfunction "GND_4") (pintype "bidirectional"))
      (node (ref "U$13") (pin "5") (pinfunction "GND_5") (pintype "bidirectional"))
      (node (ref "U$13") (pin "6") (pinfunction "GND_6") (pintype "bidirectional"))
      (node (ref "U$13") (pin "7") (pinfunction "GND_7") (pintype "bidirectional"))
      (node (ref "U$13") (pin "8") (pinfunction "GND_8") (pintype "bidirectional"))
      (node (ref "U$14") (pin "3") (pinfunction "GND_3") (pintype "bidirectional"))
      (node (ref "U$14") (pin "4") (pinfunction "GND_4") (pintype "bidirectional"))
      (node (ref "U$14") (pin "5") (pinfunction "GND_5") (pintype "bidirectional"))
      (node (ref "U$14") (pin "6") (pinfunction "GND_6") (pintype "bidirectional"))
      (node (ref "U$14") (pin "7") (pinfunction "GND_7") (pintype "bidirectional"))
      (node (ref "U$14") (pin "8") (pinfunction "GND_8") (pintype "bidirectional"))
      (node (ref "U$15") (pin "3") (pinfunction "GND_3") (pintype "bidirectional"))
      (node (ref "U$15") (pin "4") (pinfunction "GND_4") (pintype "bidirectional"))
      (node (ref "U$15") (pin "5") (pinfunction "GND_5") (pintype "bidirectional"))
      (node (ref "U$15") (pin "6") (pinfunction "GND_6") (pintype "bidirectional"))
      (node (ref "U$15") (pin "7") (pinfunction "GND_7") (pintype "bidirectional"))
      (node (ref "U$15") (pin "8") (pinfunction "GND_8") (pintype "bidirectional"))
      (node (ref "U$16") (pin "3") (pinfunction "GND_3") (pintype "bidirectional"))
      (node (ref "U$16") (pin "4") (pinfunction "GND_4") (pintype "bidirectional"))
      (node (ref "U$16") (pin "5") (pinfunction "GND_5") (pintype "bidirectional"))
      (node (ref "U$16") (pin "6") (pinfunction "GND_6") (pintype "bidirectional"))
      (node (ref "U$16") (pin "7") (pinfunction "GND_7") (pintype "bidirectional"))
      (node (ref "U$16") (pin "8") (pinfunction "GND_8") (pintype "bidirectional"))
      (node (ref "U$17") (pin "3") (pinfunction "GND_3") (pintype "bidirectional"))
      (node (ref "U$17") (pin "4") (pinfunction "GND_4") (pintype "bidirectional"))
      (node (ref "U$17") (pin "5") (pinfunction "GND_5") (pintype "bidirectional"))
      (node (ref "U$17") (pin "6") (pinfunction "GND_6") (pintype "bidirectional"))
      (node (ref "U$17") (pin "7") (pinfunction "GND_7") (pintype "bidirectional"))
      (node (ref "U$17") (pin "8") (pinfunction "GND_8") (pintype "bidirectional"))
      (node (ref "U$18") (pin "3") (pinfunction "GND_3") (pintype "bidirectional"))
      (node (ref "U$18") (pin "4") (pinfunction "GND_4") (pintype "bidirectional"))
      (node (ref "U$18") (pin "5") (pinfunction "GND_5") (pintype "bidirectional"))
      (node (ref "U$18") (pin "6") (pinfunction "GND_6") (pintype "bidirectional"))
      (node (ref "U$18") (pin "7") (pinfunction "GND_7") (pintype "bidirectional"))
      (node (ref "U$18") (pin "8") (pinfunction "GND_8") (pintype "bidirectional"))
      (node (ref "U$2") (pin "3") (pinfunction "GND_3") (pintype "bidirectional"))
      (node (ref "U$2") (pin "4") (pinfunction "GND_4") (pintype "bidirectional"))
      (node (ref "U$2") (pin "5") (pinfunction "GND_5") (pintype "bidirectional"))
      (node (ref "U$2") (pin "6") (pinfunction "GND_6") (pintype "bidirectional"))
      (node (ref "U$2") (pin "7") (pinfunction "GND_7") (pintype "bidirectional"))
      (node (ref "U$2") (pin "8") (pinfunction "GND_8") (pintype "bidirectional"))
      (node (ref "U$20") (pin "3") (pinfunction "GND_3") (pintype "bidirectional"))
      (node (ref "U$20") (pin "4") (pinfunction "GND_4") (pintype "bidirectional"))
      (node (ref "U$20") (pin "5") (pinfunction "GND_5") (pintype "bidirectional"))
      (node (ref "U$20") (pin "6") (pinfunction "GND_6") (pintype "bidirectional"))
      (node (ref "U$20") (pin "7") (pinfunction "GND_7") (pintype "bidirectional"))
      (node (ref "U$20") (pin "8") (pinfunction "GND_8") (pintype "bidirectional"))
      (node (ref "U$21") (pin "3") (pinfunction "GND_3") (pintype "bidirectional"))
      (node (ref "U$21") (pin "4") (pinfunction "GND_4") (pintype "bidirectional"))
      (node (ref "U$21") (pin "5") (pinfunction "GND_5") (pintype "bidirectional"))
      (node (ref "U$21") (pin "6") (pinfunction "GND_6") (pintype "bidirectional"))
      (node (ref "U$21") (pin "7") (pinfunction "GND_7") (pintype "bidirectional"))
      (node (ref "U$21") (pin "8") (pinfunction "GND_8") (pintype "bidirectional"))
      (node (ref "U$3") (pin "3") (pinfunction "GND_3") (pintype "bidirectional"))
      (node (ref "U$3") (pin "4") (pinfunction "GND_4") (pintype "bidirectional"))
      (node (ref "U$3") (pin "5") (pinfunction "GND_5") (pintype "bidirectional"))
      (node (ref "U$3") (pin "6") (pinfunction "GND_6") (pintype "bidirectional"))
      (node (ref "U$3") (pin "7") (pinfunction "GND_7") (pintype "bidirectional"))
      (node (ref "U$3") (pin "8") (pinfunction "GND_8") (pintype "bidirectional"))
      (node (ref "U$4") (pin "3") (pinfunction "GND_3") (pintype "bidirectional"))
      (node (ref "U$4") (pin "4") (pinfunction "GND_4") (pintype "bidirectional"))
      (node (ref "U$4") (pin "5") (pinfunction "GND_5") (pintype "bidirectional"))
      (node (ref "U$4") (pin "6") (pinfunction "GND_6") (pintype "bidirectional"))
      (node (ref "U$4") (pin "7") (pinfunction "GND_7") (pintype "bidirectional"))
      (node (ref "U$4") (pin "8") (pinfunction "GND_8") (pintype "bidirectional"))
      (node (ref "U$5") (pin "3") (pinfunction "GND_3") (pintype "bidirectional"))
      (node (ref "U$5") (pin "4") (pinfunction "GND_4") (pintype "bidirectional"))
      (node (ref "U$5") (pin "5") (pinfunction "GND_5") (pintype "bidirectional"))
      (node (ref "U$5") (pin "6") (pinfunction "GND_6") (pintype "bidirectional"))
      (node (ref "U$5") (pin "7") (pinfunction "GND_7") (pintype "bidirectional"))
      (node (ref "U$5") (pin "8") (pinfunction "GND_8") (pintype "bidirectional"))
      (node (ref "U$6") (pin "3") (pinfunction "GND_3") (pintype "bidirectional"))
      (node (ref "U$6") (pin "4") (pinfunction "GND_4") (pintype "bidirectional"))
      (node (ref "U$6") (pin "5") (pinfunction "GND_5") (pintype "bidirectional"))
      (node (ref "U$6") (pin "6") (pinfunction "GND_6") (pintype "bidirectional"))
      (node (ref "U$6") (pin "7") (pinfunction "GND_7") (pintype "bidirectional"))
      (node (ref "U$6") (pin "8") (pinfunction "GND_8") (pintype "bidirectional"))
      (node (ref "U$7") (pin "3") (pinfunction "GND_3") (pintype "bidirectional"))
      (node (ref "U$7") (pin "4") (pinfunction "GND_4") (pintype "bidirectional"))
      (node (ref "U$7") (pin "5") (pinfunction "GND_5") (pintype "bidirectional"))
      (node (ref "U$7") (pin "6") (pinfunction "GND_6") (pintype "bidirectional"))
      (node (ref "U$7") (pin "7") (pinfunction "GND_7") (pintype "bidirectional"))
      (node (ref "U$7") (pin "8") (pinfunction "GND_8") (pintype "bidirectional"))
      (node (ref "U$8") (pin "3") (pinfunction "GND_3") (pintype "bidirectional"))
      (node (ref "U$8") (pin "4") (pinfunction "GND_4") (pintype "bidirectional"))
      (node (ref "U$8") (pin "5") (pinfunction "GND_5") (pintype "bidirectional"))
      (node (ref "U$8") (pin "6") (pinfunction "GND_6") (pintype "bidirectional"))
      (node (ref "U$8") (pin "7") (pinfunction "GND_7") (pintype "bidirectional"))
      (node (ref "U$8") (pin "8") (pinfunction "GND_8") (pintype "bidirectional"))
      (node (ref "U$9") (pin "3") (pinfunction "GND_3") (pintype "bidirectional"))
      (node (ref "U$9") (pin "4") (pinfunction "GND_4") (pintype "bidirectional"))
      (node (ref "U$9") (pin "5") (pinfunction "GND_5") (pintype "bidirectional"))
      (node (ref "U$9") (pin "6") (pinfunction "GND_6") (pintype "bidirectional"))
      (node (ref "U$9") (pin "7") (pinfunction "GND_7") (pintype "bidirectional"))
      (node (ref "U$9") (pin "8") (pinfunction "GND_8") (pintype "bidirectional"))
    )
    (net (code "9") (name "Net-(D1-Pad+)") (class "Default")
      (node (ref "D1") (pin "+") (pinfunction "+_+") (pintype "passive"))
      (node (ref "R1") (pin "2") (pinfunction "2_2") (pintype "bidirectional"))
    )
    (net (code "10") (name "Net-(D2-Pad+)") (class "Default")
      (node (ref "D2") (pin "+") (pinfunction "+_+") (pintype "passive"))
      (node (ref "R2") (pin "2") (pinfunction "2_2") (pintype "bidirectional"))
    )
    (net (code "11") (name "Net-(D3-Pad+)") (class "Default")
      (node (ref "D3") (pin "+") (pinfunction "+_+") (pintype "passive"))
      (node (ref "R3") (pin "2") (pinfunction "2_2") (pintype "bidirectional"))
    )
  )
)
